# Power_5v_3v3.net
KiCad netlist of a schematic drawn in Altium Designer
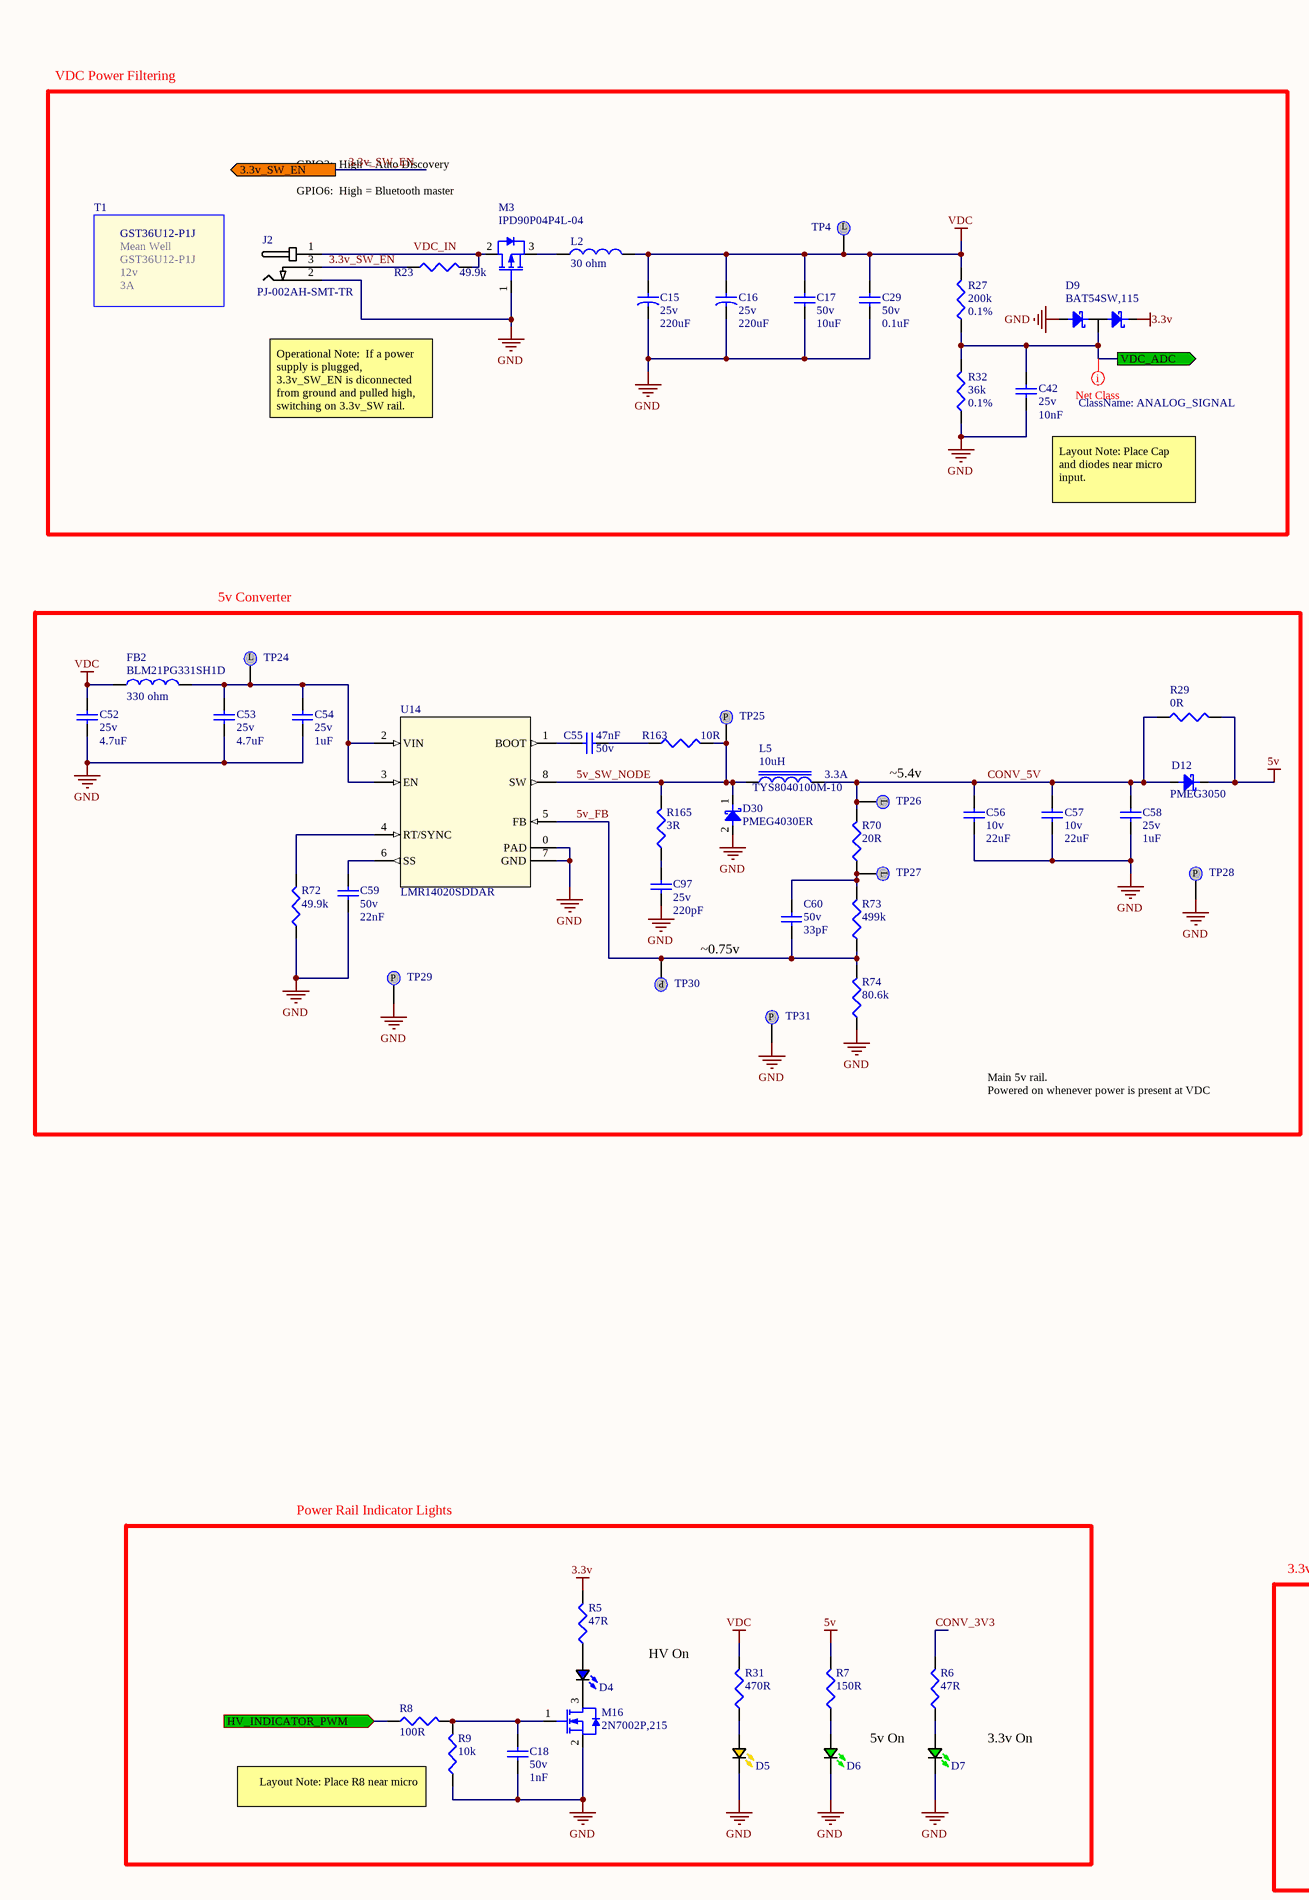
[diagram p0: Power_5v_3v3.SchDoc, left]
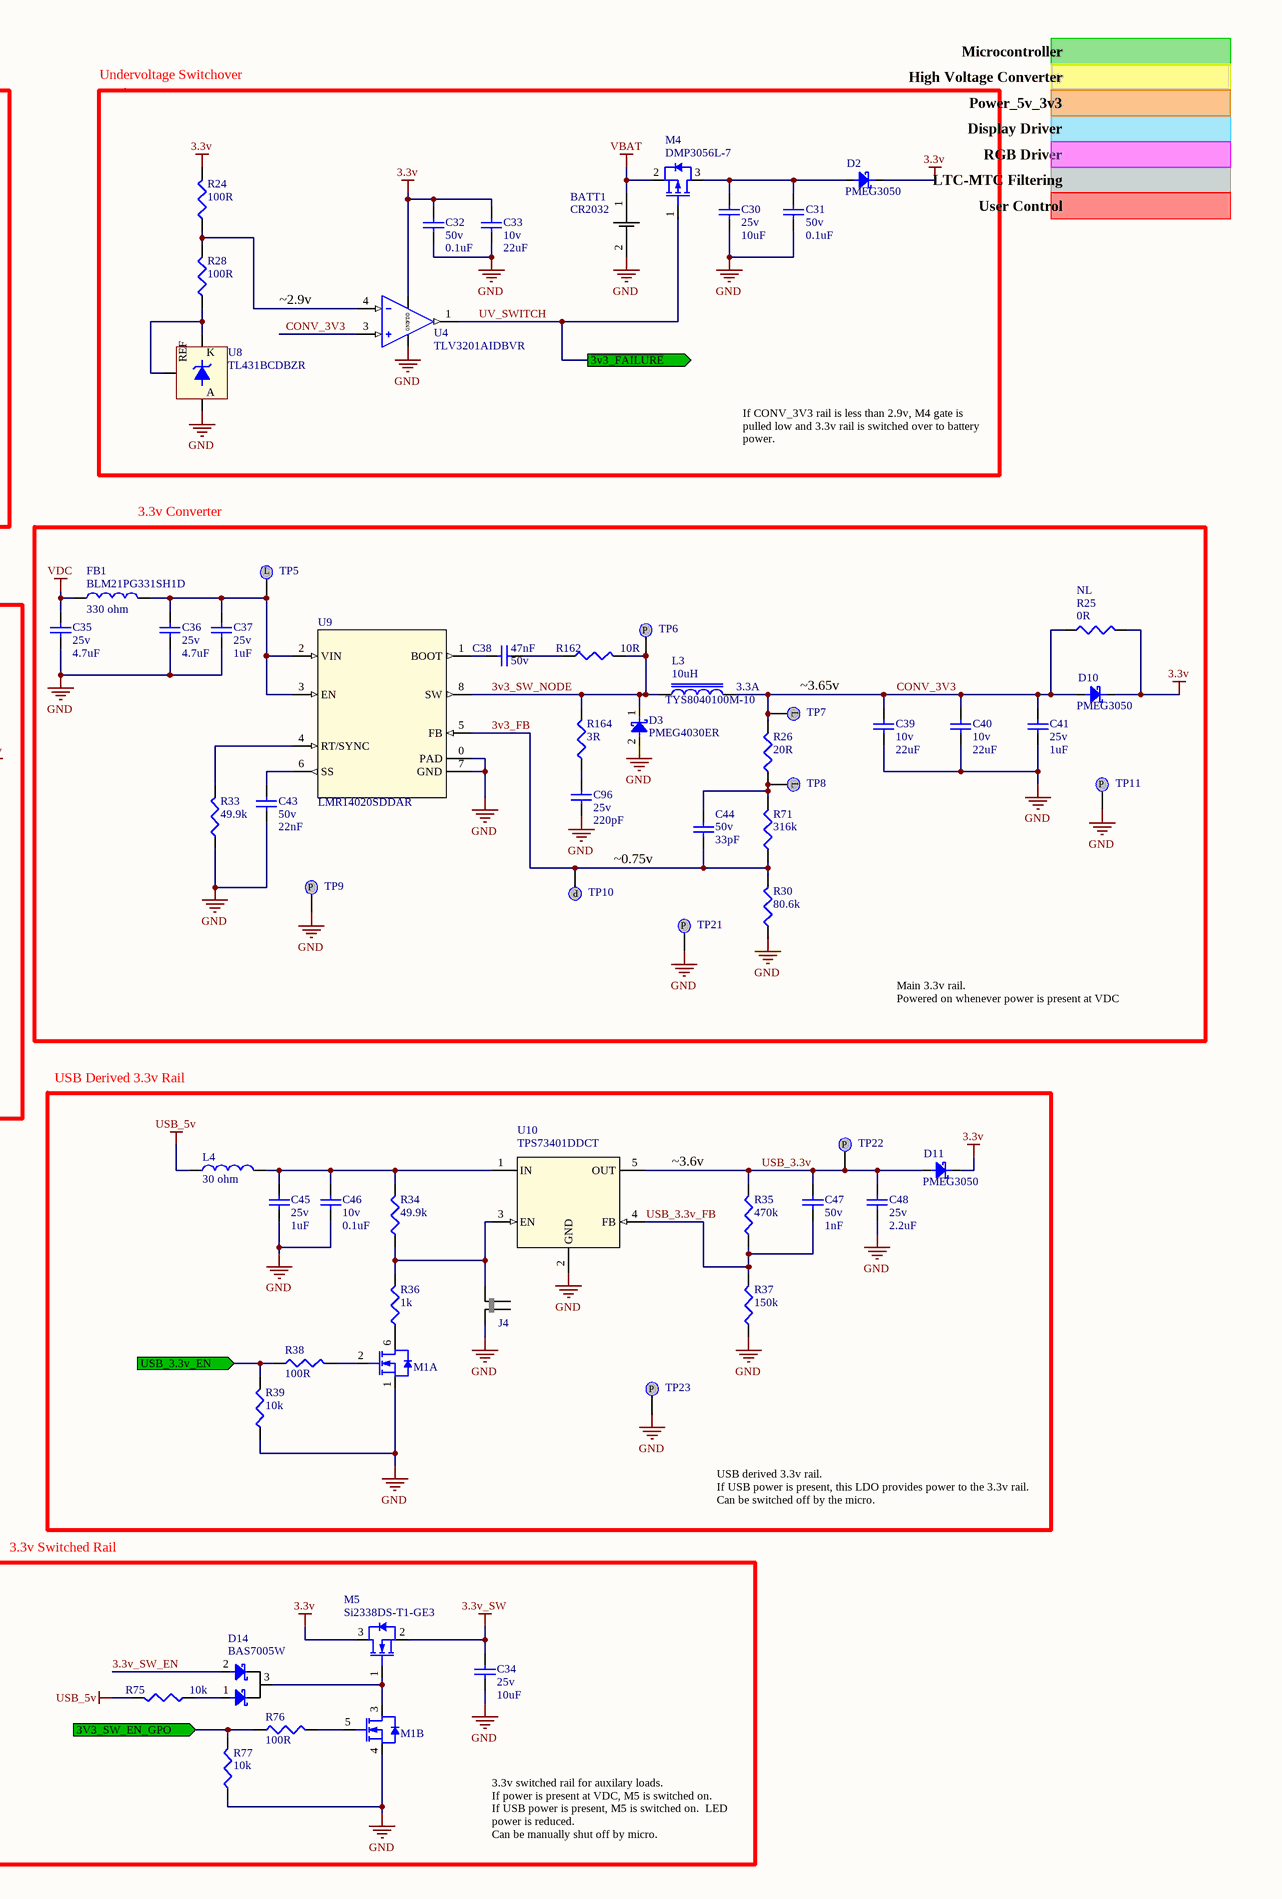
[diagram p1: Power_5v_3v3.SchDoc, right]

(export (version "E")
  (design (tool "Eeschema 10.0.6"))
  (components
    (comp (ref "BATT1")
      (value "CR2032")
      (footprint "2032 Holder")
      (description "SMD Coin Cell Holder for CR2032")
      (fields (field (name "MFG") "RENATA"))
      (libsource (lib "Altium Library") (part "2032 Coin Cell Holder"))
    )
    (comp (ref "C15")
      (value "220uF")
      (footprint "SMD ELEC CAP (D=6.3, L=7.7, H=8)")
      (fields
        (field (name "TOLERANCE") "20%")
        (field (name "MFG") "PANASONIC")
        (field (name "VOLTAGE") "25v")
      )
      (libsource (lib "Altium Library") (part "220uF / 25v"))
    )
    (comp (ref "C16")
      (value "220uF")
      (footprint "SMD ELEC CAP (D=6.3, L=7.7, H=8)")
      (fields
        (field (name "TOLERANCE") "20%")
        (field (name "MFG") "PANASONIC")
        (field (name "VOLTAGE") "25v")
      )
      (libsource (lib "Altium Library") (part "220uF / 25v"))
    )
    (comp (ref "C17")
      (value "10uF")
      (footprint "CAP1206R")
      (fields (field (name "TOLERANCE") "10%") (field (name "MFG") "TDK") (field (name "VOLTAGE") "50v"))
      (libsource (lib "Altium Library") (part "10uF 50v (1206)"))
    )
    (comp (ref "C18")
      (value "1nF")
      (footprint "CAP0402R")
      (fields (field (name "TOLERANCE") "10%") (field (name "MFG") "Vishay") (field (name "VOLTAGE") "50v"))
      (libsource (lib "Altium Library") (part "1nF 50v (0402)"))
    )
    (comp (ref "C29")
      (value "0.1uF")
      (footprint "CAP0603R")
      (fields (field (name "MFG") "Vishay") (field (name "VOLTAGE") "50v"))
      (libsource (lib "Altium Library") (part "0.1uF 50v (0603)"))
    )
    (comp (ref "C30")
      (value "10uF")
      (footprint "CAP1206R")
      (fields (field (name "TOLERANCE") "10%") (field (name "MFG") "MURATA") (field (name "VOLTAGE") "25v"))
      (libsource (lib "Altium Library") (part "10uF 25v (1206)"))
    )
    (comp (ref "C31")
      (value "0.1uF")
      (footprint "CAP0603R")
      (fields (field (name "MFG") "Vishay") (field (name "VOLTAGE") "50v"))
      (libsource (lib "Altium Library") (part "0.1uF 50v (0603)"))
    )
    (comp (ref "C32")
      (value "0.1uF")
      (footprint "CAP0603R")
      (fields (field (name "MFG") "Vishay") (field (name "VOLTAGE") "50v"))
      (libsource (lib "Altium Library") (part "0.1uF 50v (0603)"))
    )
    (comp (ref "C33")
      (value "22uF")
      (footprint "CAP1210R")
      (fields (field (name "TOLERANCE") "10%") (field (name "MFG") "MURATA") (field (name "VOLTAGE") "10v"))
      (libsource (lib "Altium Library") (part "22uF 10v (1210)"))
    )
    (comp (ref "C34")
      (value "10uF")
      (footprint "CAP1206R")
      (fields (field (name "TOLERANCE") "10%") (field (name "MFG") "MURATA") (field (name "VOLTAGE") "25v"))
      (libsource (lib "Altium Library") (part "10uF 25v (1206)"))
    )
    (comp (ref "C35")
      (value "4.7uF")
      (footprint "CAP1206R")
      (fields (field (name "TOLERANCE") "10%") (field (name "MFG") "Murata") (field (name "VOLTAGE") "25v"))
      (libsource (lib "Altium Library") (part "4.7uF 25v (1206)"))
    )
    (comp (ref "C36")
      (value "4.7uF")
      (footprint "CAP1206R")
      (fields (field (name "TOLERANCE") "10%") (field (name "MFG") "Murata") (field (name "VOLTAGE") "25v"))
      (libsource (lib "Altium Library") (part "4.7uF 25v (1206)"))
    )
    (comp (ref "C37")
      (value "1uF")
      (footprint "CAP0805R")
      (fields (field (name "MFG") "Vishay") (field (name "VOLTAGE") "25v"))
      (libsource (lib "Altium Library") (part "1uF 25v (0805)"))
    )
    (comp (ref "C38")
      (value "47nF")
      (footprint "CAP0603R")
      (fields (field (name "TOLERANCE") "10%") (field (name "MFG") "VISHAY") (field (name "VOLTAGE") "50v"))
      (libsource (lib "Altium Library") (part "47nF 50v (0603)"))
    )
    (comp (ref "C39")
      (value "22uF")
      (footprint "CAP1210R")
      (fields (field (name "TOLERANCE") "10%") (field (name "MFG") "MURATA") (field (name "VOLTAGE") "10v"))
      (libsource (lib "Altium Library") (part "22uF 10v (1210)"))
    )
    (comp (ref "C40")
      (value "22uF")
      (footprint "CAP1210R")
      (fields (field (name "TOLERANCE") "10%") (field (name "MFG") "MURATA") (field (name "VOLTAGE") "10v"))
      (libsource (lib "Altium Library") (part "22uF 10v (1210)"))
    )
    (comp (ref "C41")
      (value "1uF")
      (footprint "CAP0805R")
      (fields (field (name "MFG") "Vishay") (field (name "VOLTAGE") "25v"))
      (libsource (lib "Altium Library") (part "1uF 25v (0805)"))
    )
    (comp (ref "C42")
      (value "10nF")
      (footprint "CAP0402R")
      (fields (field (name "TOLERANCE") "5%") (field (name "MFG") "Vishay") (field (name "VOLTAGE") "25v"))
      (libsource (lib "Altium Library") (part "10nF 25v (0402)"))
    )
    (comp (ref "C43")
      (value "22nF")
      (footprint "CAP0603R")
      (fields (field (name "TOLERANCE") "5%") (field (name "VOLTAGE") "50v"))
      (libsource (lib "Altium Library") (part "22nF 50v (0603)"))
    )
    (comp (ref "C44")
      (value "33pF")
      (footprint "CAP0402R")
      (fields (field (name "TOLERANCE") "5%") (field (name "MFG") "Vishay") (field (name "VOLTAGE") "50v"))
      (libsource (lib "Altium Library") (part "33pF 50v (0402)"))
    )
    (comp (ref "C45")
      (value "1uF")
      (footprint "CAP0805R")
      (fields (field (name "MFG") "Vishay") (field (name "VOLTAGE") "25v"))
      (libsource (lib "Altium Library") (part "1uF 25v (0805)"))
    )
    (comp (ref "C46")
      (value "0.1uF")
      (footprint "CAP0402R")
      (fields (field (name "TOLERANCE") "20%") (field (name "MFG") "Vishay") (field (name "VOLTAGE") "10v"))
      (libsource (lib "Altium Library") (part "0.1uF 10v (0402)"))
    )
    (comp (ref "C47")
      (value "1nF")
      (footprint "CAP0402R")
      (fields (field (name "TOLERANCE") "10%") (field (name "MFG") "Vishay") (field (name "VOLTAGE") "50v"))
      (libsource (lib "Altium Library") (part "1nF 50v (0402)"))
    )
    (comp (ref "C48")
      (value "2.2uF")
      (footprint "CAP1206R")
      (fields (field (name "VOLTAGE") "25v"))
      (libsource (lib "Altium Library") (part "2.2uF 25v (1206)"))
    )
    (comp (ref "C52")
      (value "4.7uF")
      (footprint "CAP1206R")
      (fields (field (name "TOLERANCE") "10%") (field (name "MFG") "Murata") (field (name "VOLTAGE") "25v"))
      (libsource (lib "Altium Library") (part "4.7uF 25v (1206)"))
    )
    (comp (ref "C53")
      (value "4.7uF")
      (footprint "CAP1206R")
      (fields (field (name "TOLERANCE") "10%") (field (name "MFG") "Murata") (field (name "VOLTAGE") "25v"))
      (libsource (lib "Altium Library") (part "4.7uF 25v (1206)"))
    )
    (comp (ref "C54")
      (value "1uF")
      (footprint "CAP0805R")
      (fields (field (name "MFG") "Vishay") (field (name "VOLTAGE") "25v"))
      (libsource (lib "Altium Library") (part "1uF 25v (0805)"))
    )
    (comp (ref "C55")
      (value "47nF")
      (footprint "CAP0603R")
      (fields (field (name "TOLERANCE") "10%") (field (name "MFG") "VISHAY") (field (name "VOLTAGE") "50v"))
      (libsource (lib "Altium Library") (part "47nF 50v (0603)"))
    )
    (comp (ref "C56")
      (value "22uF")
      (footprint "CAP1210R")
      (fields (field (name "TOLERANCE") "10%") (field (name "MFG") "MURATA") (field (name "VOLTAGE") "10v"))
      (libsource (lib "Altium Library") (part "22uF 10v (1210)"))
    )
    (comp (ref "C57")
      (value "22uF")
      (footprint "CAP1210R")
      (fields (field (name "TOLERANCE") "10%") (field (name "MFG") "MURATA") (field (name "VOLTAGE") "10v"))
      (libsource (lib "Altium Library") (part "22uF 10v (1210)"))
    )
    (comp (ref "C58")
      (value "1uF")
      (footprint "CAP0805R")
      (fields (field (name "MFG") "Vishay") (field (name "VOLTAGE") "25v"))
      (libsource (lib "Altium Library") (part "1uF 25v (0805)"))
    )
    (comp (ref "C59")
      (value "22nF")
      (footprint "CAP0603R")
      (fields (field (name "TOLERANCE") "5%") (field (name "VOLTAGE") "50v"))
      (libsource (lib "Altium Library") (part "22nF 50v (0603)"))
    )
    (comp (ref "C60")
      (value "33pF")
      (footprint "CAP0402R")
      (fields (field (name "TOLERANCE") "5%") (field (name "MFG") "Vishay") (field (name "VOLTAGE") "50v"))
      (libsource (lib "Altium Library") (part "33pF 50v (0402)"))
    )
    (comp (ref "C96")
      (value "220pF")
      (footprint "CAP0402R")
      (fields (field (name "TOLERANCE") "5%") (field (name "MFG") "Murata") (field (name "VOLTAGE") "25v"))
      (libsource (lib "Altium Library") (part "220pF 25v (0402)"))
    )
    (comp (ref "C97")
      (value "220pF")
      (footprint "CAP0402R")
      (fields (field (name "TOLERANCE") "5%") (field (name "MFG") "Murata") (field (name "VOLTAGE") "25v"))
      (libsource (lib "Altium Library") (part "220pF 25v (0402)"))
    )
    (comp (ref "D2")
      (value "PMEG3050")
      (footprint "SOD128")
      (fields (field (name "MFG") "NXP"))
      (libsource (lib "Altium Library") (part "PMEG3050EP"))
    )
    (comp (ref "D3")
      (value "PMEG4030ER")
      (footprint "SOD-123")
      (fields (field (name "MFG") "NXP"))
      (libsource (lib "Altium Library") (part "PMEG4030ER"))
    )
    (comp (ref "D4")
      (value "LTST-C193TBKT-5A")
      (footprint "LED Blue 0603")
      (fields (field (name "MFG") "Lite On"))
      (libsource (lib "Altium Library") (part "LED Blue 0603"))
    )
    (comp (ref "D5")
      (value "LTST-C190AKT")
      (footprint "LED Amber 0603")
      (fields (field (name "MFG") "Lite On"))
      (libsource (lib "Altium Library") (part "LED Amber 0603"))
    )
    (comp (ref "D6")
      (value "LTST-S270KGKT")
      (footprint "LED Green 0603")
      (fields (field (name "MFG") "Lite On"))
      (libsource (lib "Altium Library") (part "LED Green 0603"))
    )
    (comp (ref "D7")
      (value "LTST-S270KGKT")
      (footprint "LED Green 0603")
      (fields (field (name "MFG") "Lite On"))
      (libsource (lib "Altium Library") (part "LED Green 0603"))
    )
    (comp (ref "D9")
      (value "BAT54SW,115")
      (footprint "SOT-323")
      (description "Series connected dual Schottky diode")
      (fields (field (name "MFG") "NXP"))
      (libsource (lib "Altium Library") (part "BAT54S"))
    )
    (comp (ref "D10")
      (value "PMEG3050")
      (footprint "SOD128")
      (fields (field (name "MFG") "NXP"))
      (libsource (lib "Altium Library") (part "PMEG3050EP"))
    )
    (comp (ref "D11")
      (value "PMEG3050")
      (footprint "SOD128")
      (fields (field (name "MFG") "NXP"))
      (libsource (lib "Altium Library") (part "PMEG3050EP"))
    )
    (comp (ref "D12")
      (value "PMEG3050")
      (footprint "SOD128")
      (fields (field (name "MFG") "NXP"))
      (libsource (lib "Altium Library") (part "PMEG3050EP"))
    )
    (comp (ref "D14")
      (value "BAS7005W")
      (footprint "SOT-323")
      (description "Schottky, Dual, Common Cathode")
      (fields (field (name "MFG") "Vishay"))
      (libsource (lib "Altium Library") (part "BAS7005WH6327XTSA1"))
    )
    (comp (ref "D30")
      (value "PMEG4030ER")
      (footprint "SOD-123")
      (fields (field (name "MFG") "NXP"))
      (libsource (lib "Altium Library") (part "PMEG4030ER"))
    )
    (comp (ref "FB1")
      (value "BLM21PG331SH1D")
      (footprint "RES0805R")
      (fields
        (field (name "MFG") "MURATA")
        (field (name "TOLERANCE") "20%")
        (field (name "IMPEDANCE") "330 ohm")
      )
      (libsource (lib "Altium Library") (part "BLM21PG331SH1D (0805)"))
    )
    (comp (ref "FB2")
      (value "BLM21PG331SH1D")
      (footprint "RES0805R")
      (fields
        (field (name "MFG") "MURATA")
        (field (name "TOLERANCE") "20%")
        (field (name "IMPEDANCE") "330 ohm")
      )
      (libsource (lib "Altium Library") (part "BLM21PG331SH1D (0805)"))
    )
    (comp (ref "J2")
      (value "PJ-002AH-SMT-TR")
      (footprint "PJ-002AH-SMT-TR")
      (description "2.0mm ID/6.5mm OD Barrel Plug")
      (fields (field (name "MFG") "CUI") (field (name "VOLTAGE") "16v"))
      (libsource (lib "Altium Library") (part "PJ-002AH-SMT-TR"))
    )
    (comp (ref "J4")
      (value "None")
      (footprint "Jumper_2.54mm_2x1")
      (description "Jumper_Single_2.54mm")
      (libsource (lib "Altium Library") (part "Jumper x1"))
    )
    (comp (ref "L2")
      (value "30 ohm")
      (footprint "RES0805R")
      (fields (field (name "MFG") "MURATA") (field (name "TOLERANCE") "20%"))
      (libsource (lib "Altium Library") (part "EMI Ferrite (0805)"))
    )
    (comp (ref "L3")
      (value "10uH")
      (footprint "TYS8040100M-10")
      (description "Inductor, 10uH, 3.3A")
      (fields
        (field (name "MFG") "LAIRD")
        (field (name "MFG_PN") "TYS8040100M-10")
        (field (name "CURRENT") "3.3A")
      )
      (libsource (lib "Altium Library") (part "10uH 3.3A"))
    )
    (comp (ref "L4")
      (value "30 ohm")
      (footprint "RES0805R")
      (fields (field (name "MFG") "MURATA") (field (name "TOLERANCE") "20%"))
      (libsource (lib "Altium Library") (part "EMI Ferrite (0805)"))
    )
    (comp (ref "L5")
      (value "10uH")
      (footprint "TYS8040100M-10")
      (description "Inductor, 10uH, 3.3A")
      (fields
        (field (name "MFG") "LAIRD")
        (field (name "MFG_PN") "TYS8040100M-10")
        (field (name "CURRENT") "3.3A")
      )
      (libsource (lib "Altium Library") (part "10uH 3.3A"))
    )
    (comp (ref "M1")
      (value "NX3020NAKV,115")
      (footprint "SOT666-6N")
      (description "NFET_DUAL_200mA_30v")
      (fields (field (name "MFG") "NXP"))
      (libsource (lib "Altium Library") (part "NX3020NAKV"))
    )
    (comp (ref "M3")
      (value "IPD90P04P4L-04")
      (footprint "DPAK2")
      (description "PFET_SINGLE_90A_40v")
      (fields (field (name "MFG") "INFINEON"))
      (libsource (lib "Altium Library") (part "IPD90P04P4L-04"))
    )
    (comp (ref "M4")
      (value "DMP3056L-7")
      (footprint "SOT23-3M")
      (description "PFET_SINGLE_4.3A_30v")
      (fields (field (name "MFG") "DIODES_INC"))
      (libsource (lib "Altium Library") (part "DMP3056L"))
    )
    (comp (ref "M5")
      (value "Si2338DS-T1-GE3")
      (footprint "SOT23-3M")
      (description "NFET_SINGLE_6A_30V")
      (fields (field (name "MFG") "VISHAY"))
      (libsource (lib "Altium Library") (part "Si2338DS"))
    )
    (comp (ref "M16")
      (value "2N7002P,215")
      (footprint "SOT23-3M")
      (description "NFET_SINGLE_360mA_60V")
      (fields (field (name "MFG") "NXP"))
      (libsource (lib "Altium Library") (part "2N7002"))
    )
    (comp (ref "R5")
      (value "47R")
      (footprint "RES0603R")
      (fields (field (name "TOLERANCE") "1%") (field (name "POWER") "0.1W") (field (name "MFG") "Vishay"))
      (libsource (lib "Altium Library") (part "47R (0603)"))
    )
    (comp (ref "R6")
      (value "47R")
      (footprint "RES0603R")
      (fields (field (name "TOLERANCE") "1%") (field (name "POWER") "0.1W") (field (name "MFG") "Vishay"))
      (libsource (lib "Altium Library") (part "47R (0603)"))
    )
    (comp (ref "R7")
      (value "150R")
      (footprint "RES0603R")
      (fields (field (name "TOLERANCE") "1%") (field (name "POWER") "0.1W") (field (name "MFG") "Vishay"))
      (libsource (lib "Altium Library") (part "150R (0603)"))
    )
    (comp (ref "R8")
      (value "100R")
      (footprint "RES0402R")
      (fields (field (name "TOLERANCE") "1%") (field (name "POWER") "63mW") (field (name "MFG") "Vishay"))
      (libsource (lib "Altium Library") (part "100R (0402)"))
    )
    (comp (ref "R9")
      (value "10k")
      (footprint "RES0402R")
      (fields (field (name "TOLERANCE") "1%") (field (name "POWER") "63mW") (field (name "MFG") "Vishay"))
      (libsource (lib "Altium Library") (part "10k (0402)"))
    )
    (comp (ref "R23")
      (value "49.9k")
      (footprint "RES0402R")
      (fields (field (name "TOLERANCE") "1%") (field (name "POWER") "63mW") (field (name "MFG") "Vishay"))
      (libsource (lib "Altium Library") (part "49.9k (0402)"))
    )
    (comp (ref "R24")
      (value "100R")
      (footprint "RES0402R")
      (fields (field (name "TOLERANCE") "1%") (field (name "POWER") "63mW") (field (name "MFG") "Vishay"))
      (libsource (lib "Altium Library") (part "100R (0402)"))
    )
    (comp (ref "R25")
      (value "0R")
      (footprint "RES1206R")
      (description "0R, 1206")
      (fields (field (name "MFG") "Vishay") (field (name "LOAD") "NL"))
      (libsource (lib "Altium Library") (part "0R (1206)"))
    )
    (comp (ref "R26")
      (value "20R")
      (footprint "RES0402R")
      (fields (field (name "TOLERANCE") "1%") (field (name "POWER") "63mW") (field (name "MFG") "Vishay"))
      (libsource (lib "Altium Library") (part "20R (0402)"))
    )
    (comp (ref "R27")
      (value "200k")
      (footprint "RES0402R")
      (fields (field (name "POWER") "63mW") (field (name "MFG") "Vishay") (field (name "TOLERANCE") "0.1%"))
      (libsource (lib "Altium Library") (part "200k   0.1% (0402)"))
    )
    (comp (ref "R28")
      (value "100R")
      (footprint "RES0402R")
      (fields (field (name "TOLERANCE") "1%") (field (name "POWER") "63mW") (field (name "MFG") "Vishay"))
      (libsource (lib "Altium Library") (part "100R (0402)"))
    )
    (comp (ref "R29")
      (value "0R")
      (footprint "RES1206R")
      (description "0R, 1206")
      (fields (field (name "MFG") "Vishay"))
      (libsource (lib "Altium Library") (part "0R (1206)"))
    )
    (comp (ref "R30")
      (value "80.6k")
      (footprint "RES0402R")
      (fields (field (name "TOLERANCE") "1%") (field (name "POWER") "63mW") (field (name "MFG") "Vishay"))
      (libsource (lib "Altium Library") (part "80.6k (0402)"))
    )
    (comp (ref "R31")
      (value "470R")
      (footprint "RES0603R")
      (fields (field (name "TOLERANCE") "1%") (field (name "POWER") "0.1W") (field (name "MFG") "Vishay"))
      (libsource (lib "Altium Library") (part "470R (0603)"))
    )
    (comp (ref "R32")
      (value "36k")
      (footprint "RES0402R")
      (fields (field (name "POWER") "63mW") (field (name "MFG") "Vishay") (field (name "TOLERANCE") "0.1%"))
      (libsource (lib "Altium Library") (part "36k   0.1% (0402)"))
    )
    (comp (ref "R33")
      (value "49.9k")
      (footprint "RES0402R")
      (fields (field (name "TOLERANCE") "1%") (field (name "POWER") "63mW") (field (name "MFG") "Vishay"))
      (libsource (lib "Altium Library") (part "49.9k (0402)"))
    )
    (comp (ref "R34")
      (value "49.9k")
      (footprint "RES0402R")
      (fields (field (name "TOLERANCE") "1%") (field (name "POWER") "63mW") (field (name "MFG") "Vishay"))
      (libsource (lib "Altium Library") (part "49.9k (0402)"))
    )
    (comp (ref "R35")
      (value "470k")
      (footprint "RES0402R")
      (fields (field (name "TOLERANCE") "1%") (field (name "POWER") "63mW") (field (name "MFG") "Vishay"))
      (libsource (lib "Altium Library") (part "470k (0402)"))
    )
    (comp (ref "R36")
      (value "1k")
      (footprint "RES0402R")
      (fields (field (name "TOLERANCE") "1%") (field (name "POWER") "63mW") (field (name "MFG") "Vishay"))
      (libsource (lib "Altium Library") (part "1k (0402)"))
    )
    (comp (ref "R37")
      (value "150k")
      (footprint "RES0402R")
      (fields (field (name "TOLERANCE") "1%") (field (name "POWER") "63mW") (field (name "MFG") "Vishay"))
      (libsource (lib "Altium Library") (part "150k (0402)"))
    )
    (comp (ref "R38")
      (value "100R")
      (footprint "RES0402R")
      (fields (field (name "TOLERANCE") "1%") (field (name "POWER") "63mW") (field (name "MFG") "Vishay"))
      (libsource (lib "Altium Library") (part "100R (0402)"))
    )
    (comp (ref "R39")
      (value "10k")
      (footprint "RES0402R")
      (fields (field (name "TOLERANCE") "1%") (field (name "POWER") "63mW") (field (name "MFG") "Vishay"))
      (libsource (lib "Altium Library") (part "10k (0402)"))
    )
    (comp (ref "R70")
      (value "20R")
      (footprint "RES0402R")
      (fields (field (name "TOLERANCE") "1%") (field (name "POWER") "63mW") (field (name "MFG") "Vishay"))
      (libsource (lib "Altium Library") (part "20R (0402)"))
    )
    (comp (ref "R71")
      (value "316k")
      (footprint "RES0402R")
      (fields (field (name "TOLERANCE") "1%") (field (name "POWER") "63mW") (field (name "MFG") "Vishay"))
      (libsource (lib "Altium Library") (part "316k (0402)"))
    )
    (comp (ref "R72")
      (value "49.9k")
      (footprint "RES0402R")
      (fields (field (name "TOLERANCE") "1%") (field (name "POWER") "63mW") (field (name "MFG") "Vishay"))
      (libsource (lib "Altium Library") (part "49.9k (0402)"))
    )
    (comp (ref "R73")
      (value "499k")
      (footprint "RES0402R")
      (fields (field (name "TOLERANCE") "1%") (field (name "POWER") "63mW") (field (name "MFG") "Vishay"))
      (libsource (lib "Altium Library") (part "499k (0402)"))
    )
    (comp (ref "R74")
      (value "80.6k")
      (footprint "RES0402R")
      (fields (field (name "TOLERANCE") "1%") (field (name "POWER") "63mW") (field (name "MFG") "Vishay"))
      (libsource (lib "Altium Library") (part "80.6k (0402)"))
    )
    (comp (ref "R75")
      (value "10k")
      (footprint "RES0402R")
      (fields (field (name "TOLERANCE") "1%") (field (name "POWER") "63mW") (field (name "MFG") "Vishay"))
      (libsource (lib "Altium Library") (part "10k (0402)"))
    )
    (comp (ref "R76")
      (value "100R")
      (footprint "RES0402R")
      (fields (field (name "TOLERANCE") "1%") (field (name "POWER") "63mW") (field (name "MFG") "Vishay"))
      (libsource (lib "Altium Library") (part "100R (0402)"))
    )
    (comp (ref "R77")
      (value "10k")
      (footprint "RES0402R")
      (fields (field (name "TOLERANCE") "1%") (field (name "POWER") "63mW") (field (name "MFG") "Vishay"))
      (libsource (lib "Altium Library") (part "10k (0402)"))
    )
    (comp (ref "R162")
      (value "10R")
      (footprint "RES0402R")
      (fields (field (name "TOLERANCE") "1%") (field (name "POWER") "63mW") (field (name "MFG") "Vishay"))
      (libsource (lib "Altium Library") (part "10R (0402)"))
    )
    (comp (ref "R163")
      (value "10R")
      (footprint "RES0402R")
      (fields (field (name "TOLERANCE") "1%") (field (name "POWER") "63mW") (field (name "MFG") "Vishay"))
      (libsource (lib "Altium Library") (part "10R (0402)"))
    )
    (comp (ref "R164")
      (value "3R")
      (footprint "RES0603R")
      (fields (field (name "TOLERANCE") "1%") (field (name "POWER") "0.1W") (field (name "MFG") "Vishay"))
      (libsource (lib "Altium Library") (part "3R (0603)"))
    )
    (comp (ref "R165")
      (value "3R")
      (footprint "RES0603R")
      (fields (field (name "TOLERANCE") "1%") (field (name "POWER") "0.1W") (field (name "MFG") "Vishay"))
      (libsource (lib "Altium Library") (part "3R (0603)"))
    )
    (comp (ref "T1")
      (value "GST36U12-P1J")
      (description "12v/3A Wall Mount AC Adapter")
      (fields
        (field (name "MFG") "Mean Well")
        (field (name "MFG_PN") "GST36U12-P1J")
        (field (name "VOUT") "12v")
        (field (name "CURRENT") "3A")
      )
      (libsource (lib "Altium Library") (part "GST36U12-P1J"))
    )
    (comp (ref "TP4")
      (value "5001")
      (footprint "5001 Testpoint")
      (fields (field (name "MFG") "KEYSTONE"))
      (libsource (lib "Altium Library") (part "Testpoint Loop"))
    )
    (comp (ref "TP5")
      (value "5001")
      (footprint "5001 Testpoint")
      (fields (field (name "MFG") "KEYSTONE"))
      (libsource (lib "Altium Library") (part "Testpoint Loop"))
    )
    (comp (ref "TP6")
      (value "NONE")
      (footprint "TESTPOINT - 1.5mm Round Pad")
      (description "1.5mm Testpoint")
      (libsource (lib "Altium Library") (part "Testpoint 1.5mm Pad"))
    )
    (comp (ref "TP7")
      (value "5001")
      (footprint "5001 Testpoint")
      (fields (field (name "MFG") "KEYSTONE"))
      (libsource (lib "Altium Library") (part "Testpoint Loop"))
    )
    (comp (ref "TP8")
      (value "5001")
      (footprint "5001 Testpoint")
      (fields (field (name "MFG") "KEYSTONE"))
      (libsource (lib "Altium Library") (part "Testpoint Loop"))
    )
    (comp (ref "TP9")
      (value "NONE")
      (footprint "TESTPOINT - 1.5mm Round Pad")
      (description "1.5mm Testpoint")
      (libsource (lib "Altium Library") (part "Testpoint 1.5mm Pad"))
    )
    (comp (ref "TP10")
      (value "NONE")
      (footprint "TESTPOINT - 1.5mm Round Pad")
      (description "1.5mm Testpoint")
      (libsource (lib "Altium Library") (part "Testpoint 1.5mm Pad"))
    )
    (comp (ref "TP11")
      (value "NONE")
      (footprint "TESTPOINT - 1.5mm Round Pad")
      (description "1.5mm Testpoint")
      (libsource (lib "Altium Library") (part "Testpoint 1.5mm Pad"))
    )
    (comp (ref "TP21")
      (value "NONE")
      (footprint "TESTPOINT - 1.5mm Round Pad")
      (description "1.5mm Testpoint")
      (libsource (lib "Altium Library") (part "Testpoint 1.5mm Pad"))
    )
    (comp (ref "TP22")
      (value "NONE")
      (footprint "TESTPOINT - 1.5mm Round Pad")
      (description "1.5mm Testpoint")
      (libsource (lib "Altium Library") (part "Testpoint 1.5mm Pad"))
    )
    (comp (ref "TP23")
      (value "NONE")
      (footprint "TESTPOINT - 1.5mm Round Pad")
      (description "1.5mm Testpoint")
      (libsource (lib "Altium Library") (part "Testpoint 1.5mm Pad"))
    )
    (comp (ref "TP24")
      (value "5001")
      (footprint "5001 Testpoint")
      (fields (field (name "MFG") "KEYSTONE"))
      (libsource (lib "Altium Library") (part "Testpoint Loop"))
    )
    (comp (ref "TP25")
      (value "NONE")
      (footprint "TESTPOINT - 1.5mm Round Pad")
      (description "1.5mm Testpoint")
      (libsource (lib "Altium Library") (part "Testpoint 1.5mm Pad"))
    )
    (comp (ref "TP26")
      (value "5001")
      (footprint "5001 Testpoint")
      (fields (field (name "MFG") "KEYSTONE"))
      (libsource (lib "Altium Library") (part "Testpoint Loop"))
    )
    (comp (ref "TP27")
      (value "5001")
      (footprint "5001 Testpoint")
      (fields (field (name "MFG") "KEYSTONE"))
      (libsource (lib "Altium Library") (part "Testpoint Loop"))
    )
    (comp (ref "TP28")
      (value "NONE")
      (footprint "TESTPOINT - 1.5mm Round Pad")
      (description "1.5mm Testpoint")
      (libsource (lib "Altium Library") (part "Testpoint 1.5mm Pad"))
    )
    (comp (ref "TP29")
      (value "NONE")
      (footprint "TESTPOINT - 1.5mm Round Pad")
      (description "1.5mm Testpoint")
      (libsource (lib "Altium Library") (part "Testpoint 1.5mm Pad"))
    )
    (comp (ref "TP30")
      (value "NONE")
      (footprint "TESTPOINT - 1.5mm Round Pad")
      (description "1.5mm Testpoint")
      (libsource (lib "Altium Library") (part "Testpoint 1.5mm Pad"))
    )
    (comp (ref "TP31")
      (value "NONE")
      (footprint "TESTPOINT - 1.5mm Round Pad")
      (description "1.5mm Testpoint")
      (libsource (lib "Altium Library") (part "Testpoint 1.5mm Pad"))
    )
    (comp (ref "U4")
      (value "TLV3201AIDBVR")
      (footprint "SOT23-5")
      (description "High Speed Analog Comparator")
      (fields (field (name "MFG") "TI"))
      (libsource (lib "Altium Library") (part "TLV3201AIDBVR"))
    )
    (comp (ref "U8")
      (value "TL431BCDBZR")
      (footprint "SOT23-3M")
      (description "Voltage Reference")
      (fields (field (name "MFG") "TI"))
      (libsource (lib "Altium Library") (part "TL431"))
    )
    (comp (ref "U9")
      (value "LMR14020SDDAR")
      (footprint "HSOIC-8")
      (description "Buck Regulator, Adjustable, 2A")
      (fields (field (name "MFG") "TI"))
      (libsource (lib "Altium Library") (part "LMR14020SDDAR"))
    )
    (comp (ref "U10")
      (value "TPS73401DDCT")
      (footprint "SOT23-5")
      (description "TPS73401DDCT, LDO, 250mA, Adj")
      (fields (field (name "MFG") "TI"))
      (libsource (lib "Altium Library") (part "TPS73401DDCT"))
    )
    (comp (ref "U14")
      (value "LMR14020SDDAR")
      (footprint "HSOIC-8")
      (description "Buck Regulator, Adjustable, 2A")
      (fields (field (name "MFG") "TI"))
      (libsource (lib "Altium Library") (part "LMR14020SDDAR"))
    )
  )
  (nets
    (net (code "1") (name "/3.3v_SW_EN") (class "Default")
      (node (ref "D14") (pin "2") (pinfunction "A2_2") (pintype "passive"))
      (node (ref "J2") (pin "3") (pinfunction "SWITCH_3") (pintype "passive"))
      (node (ref "R23") (pin "1") (pinfunction "1_1") (pintype "passive"))
    )
    (net (code "2") (name "/3V3_SW_EN_GPO") (class "Default")
      (node (ref "R76") (pin "1") (pinfunction "1_1") (pintype "passive"))
      (node (ref "R77") (pin "2") (pinfunction "2_2") (pintype "passive"))
    )
    (net (code "3") (name "/3v3_FB") (class "Default")
      (node (ref "C44") (pin "2") (pinfunction "2_2") (pintype "passive"))
      (node (ref "R30") (pin "2") (pinfunction "2_2") (pintype "passive"))
      (node (ref "R71") (pin "1") (pinfunction "1_1") (pintype "passive"))
      (node (ref "TP10") (pin "1") (pinfunction "1_1") (pintype "passive"))
      (node (ref "U9") (pin "5") (pinfunction "FB_5") (pintype "input"))
    )
    (net (code "4") (name "/3v3_SW_NODE") (class "Default")
      (node (ref "D3") (pin "1") (pinfunction "K_1") (pintype "passive"))
      (node (ref "L3") (pin "1") (pinfunction "1_1") (pintype "passive"))
      (node (ref "R162") (pin "2") (pinfunction "2_2") (pintype "passive"))
      (node (ref "R164") (pin "2") (pinfunction "2_2") (pintype "passive"))
      (node (ref "TP6") (pin "1") (pinfunction "1_1") (pintype "passive"))
      (node (ref "U9") (pin "8") (pinfunction "SW_8") (pintype "output"))
    )
    (net (code "5") (name "/5v_FB") (class "Default")
      (node (ref "C60") (pin "2") (pinfunction "2_2") (pintype "passive"))
      (node (ref "R73") (pin "1") (pinfunction "1_1") (pintype "passive"))
      (node (ref "R74") (pin "2") (pinfunction "2_2") (pintype "passive"))
      (node (ref "TP30") (pin "1") (pinfunction "1_1") (pintype "passive"))
      (node (ref "U14") (pin "5") (pinfunction "FB_5") (pintype "input"))
    )
    (net (code "6") (name "/5v_SW_NODE") (class "Default")
      (node (ref "D30") (pin "1") (pinfunction "K_1") (pintype "passive"))
      (node (ref "L5") (pin "1") (pinfunction "1_1") (pintype "passive"))
      (node (ref "R163") (pin "2") (pinfunction "2_2") (pintype "passive"))
      (node (ref "R165") (pin "2") (pinfunction "2_2") (pintype "passive"))
      (node (ref "TP25") (pin "1") (pinfunction "1_1") (pintype "passive"))
      (node (ref "U14") (pin "8") (pinfunction "SW_8") (pintype "output"))
    )
    (net (code "7") (name "/CONV_3V3") (class "Default")
      (node (ref "C39") (pin "1") (pinfunction "1_1") (pintype "passive"))
      (node (ref "C40") (pin "1") (pinfunction "1_1") (pintype "passive"))
      (node (ref "C41") (pin "1") (pinfunction "1_1") (pintype "passive"))
      (node (ref "D10") (pin "2") (pinfunction "A_2") (pintype "passive"))
      (node (ref "L3") (pin "2") (pinfunction "2_2") (pintype "passive"))
      (node (ref "R25") (pin "1") (pinfunction "1_1") (pintype "passive"))
      (node (ref "R26") (pin "2") (pinfunction "2_2") (pintype "passive"))
      (node (ref "R6") (pin "2") (pinfunction "2_2") (pintype "passive"))
      (node (ref "TP7") (pin "1") (pinfunction "1_1") (pintype "passive"))
      (node (ref "U4") (pin "3") (pinfunction "+_3") (pintype "input"))
    )
    (net (code "8") (name "/CONV_5V") (class "Default")
      (node (ref "C56") (pin "1") (pinfunction "1_1") (pintype "passive"))
      (node (ref "C57") (pin "1") (pinfunction "1_1") (pintype "passive"))
      (node (ref "C58") (pin "1") (pinfunction "1_1") (pintype "passive"))
      (node (ref "D12") (pin "2") (pinfunction "A_2") (pintype "passive"))
      (node (ref "L5") (pin "2") (pinfunction "2_2") (pintype "passive"))
      (node (ref "R29") (pin "1") (pinfunction "1_1") (pintype "passive"))
      (node (ref "R70") (pin "2") (pinfunction "2_2") (pintype "passive"))
      (node (ref "TP26") (pin "1") (pinfunction "1_1") (pintype "passive"))
    )
    (net (code "9") (name "/HV_INDICATOR_PWM") (class "Default")
      (node (ref "R8") (pin "1") (pinfunction "1_1") (pintype "passive"))
    )
    (net (code "10") (name "/USB_3.3v") (class "Default")
      (node (ref "C47") (pin "1") (pinfunction "1_1") (pintype "passive"))
      (node (ref "C48") (pin "1") (pinfunction "1_1") (pintype "passive"))
      (node (ref "D11") (pin "2") (pinfunction "A_2") (pintype "passive"))
      (node (ref "R35") (pin "2") (pinfunction "2_2") (pintype "passive"))
      (node (ref "TP22") (pin "1") (pinfunction "1_1") (pintype "passive"))
      (node (ref "U10") (pin "5") (pinfunction "OUT_5") (pintype "power_in"))
    )
    (net (code "11") (name "/USB_3.3v_EN") (class "Default")
      (node (ref "R38") (pin "1") (pinfunction "1_1") (pintype "passive"))
      (node (ref "R39") (pin "2") (pinfunction "2_2") (pintype "passive"))
    )
    (net (code "12") (name "/USB_3.3v_FB") (class "Default")
      (node (ref "C47") (pin "2") (pinfunction "2_2") (pintype "passive"))
      (node (ref "R35") (pin "1") (pinfunction "1_1") (pintype "passive"))
      (node (ref "R37") (pin "2") (pinfunction "2_2") (pintype "passive"))
      (node (ref "U10") (pin "4") (pinfunction "FB_4") (pintype "input"))
    )
    (net (code "13") (name "/UV_SWITCH") (class "Default")
      (node (ref "M4") (pin "1") (pinfunction "GATE_1") (pintype "passive"))
      (node (ref "U4") (pin "1") (pinfunction "OUT_1") (pintype "output"))
    )
    (net (code "14") (name "/VDC_ADC") (class "Default")
      (node (ref "C42") (pin "1") (pinfunction "1_1") (pintype "passive"))
      (node (ref "D9") (pin "3") (pinfunction "AK_3") (pintype "passive"))
      (node (ref "R27") (pin "1") (pinfunction "1_1") (pintype "passive"))
      (node (ref "R32") (pin "2") (pinfunction "2_2") (pintype "passive"))
    )
    (net (code "15") (name "/VDC_IN") (class "Default")
      (node (ref "J2") (pin "1") (pinfunction "PIN_1") (pintype "passive"))
      (node (ref "M3") (pin "2") (pinfunction "DRAIN_2") (pintype "passive"))
      (node (ref "R23") (pin "2") (pinfunction "2_2") (pintype "passive"))
    )
    (net (code "16") (name "3.3v") (class "Default")
      (node (ref "C32") (pin "1") (pinfunction "1_1") (pintype "passive"))
      (node (ref "C33") (pin "1") (pinfunction "1_1") (pintype "passive"))
      (node (ref "D10") (pin "1") (pinfunction "K_1") (pintype "passive"))
      (node (ref "D11") (pin "1") (pinfunction "K_1") (pintype "passive"))
      (node (ref "D2") (pin "1") (pinfunction "K_1") (pintype "passive"))
      (node (ref "D9") (pin "2") (pinfunction "A_2") (pintype "passive"))
      (node (ref "M5") (pin "3") (pinfunction "DRAIN_3") (pintype "passive"))
      (node (ref "R24") (pin "2") (pinfunction "2_2") (pintype "passive"))
      (node (ref "R25") (pin "2") (pinfunction "2_2") (pintype "passive"))
      (node (ref "R5") (pin "2") (pinfunction "2_2") (pintype "passive"))
      (node (ref "U4") (pin "5") (pinfunction "VDD_5") (pintype "passive"))
    )
    (net (code "17") (name "3.3v_SW") (class "Default")
      (node (ref "C34") (pin "1") (pinfunction "1_1") (pintype "passive"))
      (node (ref "M5") (pin "2") (pinfunction "SOURCE_2") (pintype "passive"))
    )
    (net (code "18") (name "5v") (class "Default")
      (node (ref "D12") (pin "1") (pinfunction "K_1") (pintype "passive"))
      (node (ref "R29") (pin "2") (pinfunction "2_2") (pintype "passive"))
      (node (ref "R7") (pin "2") (pinfunction "2_2") (pintype "passive"))
    )
    (net (code "19") (name "GND") (class "Default")
      (node (ref "BATT1") (pin "2") (pinfunction "2_2") (pintype "passive"))
      (node (ref "C15") (pin "1") (pinfunction "1_1") (pintype "passive"))
      (node (ref "C16") (pin "1") (pinfunction "1_1") (pintype "passive"))
      (node (ref "C17") (pin "2") (pinfunction "2_2") (pintype "passive"))
      (node (ref "C18") (pin "2") (pinfunction "2_2") (pintype "passive"))
      (node (ref "C29") (pin "2") (pinfunction "2_2") (pintype "passive"))
      (node (ref "C30") (pin "2") (pinfunction "2_2") (pintype "passive"))
      (node (ref "C31") (pin "2") (pinfunction "2_2") (pintype "passive"))
      (node (ref "C32") (pin "2") (pinfunction "2_2") (pintype "passive"))
      (node (ref "C33") (pin "2") (pinfunction "2_2") (pintype "passive"))
      (node (ref "C34") (pin "2") (pinfunction "2_2") (pintype "passive"))
      (node (ref "C35") (pin "2") (pinfunction "2_2") (pintype "passive"))
      (node (ref "C36") (pin "2") (pinfunction "2_2") (pintype "passive"))
      (node (ref "C37") (pin "2") (pinfunction "2_2") (pintype "passive"))
      (node (ref "C39") (pin "2") (pinfunction "2_2") (pintype "passive"))
      (node (ref "C40") (pin "2") (pinfunction "2_2") (pintype "passive"))
      (node (ref "C41") (pin "2") (pinfunction "2_2") (pintype "passive"))
      (node (ref "C42") (pin "2") (pinfunction "2_2") (pintype "passive"))
      (node (ref "C43") (pin "2") (pinfunction "2_2") (pintype "passive"))
      (node (ref "C45") (pin "2") (pinfunction "2_2") (pintype "passive"))
      (node (ref "C46") (pin "2") (pinfunction "2_2") (pintype "passive"))
      (node (ref "C48") (pin "2") (pinfunction "2_2") (pintype "passive"))
      (node (ref "C52") (pin "2") (pinfunction "2_2") (pintype "passive"))
      (node (ref "C53") (pin "2") (pinfunction "2_2") (pintype "passive"))
      (node (ref "C54") (pin "2") (pinfunction "2_2") (pintype "passive"))
      (node (ref "C56") (pin "2") (pinfunction "2_2") (pintype "passive"))
      (node (ref "C57") (pin "2") (pinfunction "2_2") (pintype "passive"))
      (node (ref "C58") (pin "2") (pinfunction "2_2") (pintype "passive"))
      (node (ref "C59") (pin "2") (pinfunction "2_2") (pintype "passive"))
      (node (ref "C96") (pin "2") (pinfunction "2_2") (pintype "passive"))
      (node (ref "C97") (pin "2") (pinfunction "2_2") (pintype "passive"))
      (node (ref "D3") (pin "2") (pinfunction "A_2") (pintype "passive"))
      (node (ref "D30") (pin "2") (pinfunction "A_2") (pintype "passive"))
      (node (ref "D5") (pin "1") (pinfunction "K_1") (pintype "passive"))
      (node (ref "D6") (pin "1") (pinfunction "K_1") (pintype "passive"))
      (node (ref "D7") (pin "1") (pinfunction "K_1") (pintype "passive"))
      (node (ref "D9") (pin "1") (pinfunction "A_1") (pintype "passive"))
      (node (ref "J2") (pin "2") (pinfunction "RING_2") (pintype "passive"))
      (node (ref "J4") (pin "1") (pinfunction "1_1") (pintype "passive"))
      (node (ref "M1") (pin "1") (pinfunction "S1_1") (pintype "passive"))
      (node (ref "M1") (pin "4") (pinfunction "S2_4") (pintype "passive"))
      (node (ref "M16") (pin "2") (pinfunction "SOURCE_2") (pintype "passive"))
      (node (ref "M3") (pin "1") (pinfunction "GATE_1") (pintype "passive"))
      (node (ref "R30") (pin "1") (pinfunction "1_1") (pintype "passive"))
      (node (ref "R32") (pin "1") (pinfunction "1_1") (pintype "passive"))
      (node (ref "R33") (pin "1") (pinfunction "1_1") (pintype "passive"))
      (node (ref "R37") (pin "1") (pinfunction "1_1") (pintype "passive"))
      (node (ref "R39") (pin "1") (pinfunction "1_1") (pintype "passive"))
      (node (ref "R72") (pin "1") (pinfunction "1_1") (pintype "passive"))
      (node (ref "R74") (pin "1") (pinfunction "1_1") (pintype "passive"))
      (node (ref "R77") (pin "1") (pinfunction "1_1") (pintype "passive"))
      (node (ref "R9") (pin "1") (pinfunction "1_1") (pintype "passive"))
      (node (ref "TP11") (pin "1") (pinfunction "1_1") (pintype "passive"))
      (node (ref "TP21") (pin "1") (pinfunction "1_1") (pintype "passive"))
      (node (ref "TP23") (pin "1") (pinfunction "1_1") (pintype "passive"))
      (node (ref "TP28") (pin "1") (pinfunction "1_1") (pintype "passive"))
      (node (ref "TP29") (pin "1") (pinfunction "1_1") (pintype "passive"))
      (node (ref "TP31") (pin "1") (pinfunction "1_1") (pintype "passive"))
      (node (ref "TP9") (pin "1") (pinfunction "1_1") (pintype "passive"))
      (node (ref "U10") (pin "2") (pinfunction "GND_2") (pintype "power_in"))
      (node (ref "U14") (pin "0") (pinfunction "PAD_0") (pintype "power_in"))
      (node (ref "U14") (pin "7") (pinfunction "GND_7") (pintype "power_in"))
      (node (ref "U4") (pin "2") (pinfunction "GND_2") (pintype "passive"))
      (node (ref "U8") (pin "3") (pinfunction "A_3") (pintype "power_in"))
      (node (ref "U9") (pin "0") (pinfunction "PAD_0") (pintype "power_in"))
      (node (ref "U9") (pin "7") (pinfunction "GND_7") (pintype "power_in"))
    )
    (net (code "20") (name "Net-(C38-Pad2)") (class "Default")
      (node (ref "C38") (pin "2") (pinfunction "2_2") (pintype "passive"))
      (node (ref "R162") (pin "1") (pinfunction "1_1") (pintype "passive"))
    )
    (net (code "21") (name "Net-(C44-Pad1)") (class "Default")
      (node (ref "C44") (pin "1") (pinfunction "1_1") (pintype "passive"))
      (node (ref "R26") (pin "1") (pinfunction "1_1") (pintype "passive"))
      (node (ref "R71") (pin "2") (pinfunction "2_2") (pintype "passive"))
      (node (ref "TP8") (pin "1") (pinfunction "1_1") (pintype "passive"))
    )
    (net (code "22") (name "Net-(C55-Pad2)") (class "Default")
      (node (ref "C55") (pin "2") (pinfunction "2_2") (pintype "passive"))
      (node (ref "R163") (pin "1") (pinfunction "1_1") (pintype "passive"))
    )
    (net (code "23") (name "Net-(C60-Pad1)") (class "Default")
      (node (ref "C60") (pin "1") (pinfunction "1_1") (pintype "passive"))
      (node (ref "R70") (pin "1") (pinfunction "1_1") (pintype "passive"))
      (node (ref "R73") (pin "2") (pinfunction "2_2") (pintype "passive"))
      (node (ref "TP27") (pin "1") (pinfunction "1_1") (pintype "passive"))
    )
    (net (code "24") (name "Net-(C96-Pad1)") (class "Default")
      (node (ref "C96") (pin "1") (pinfunction "1_1") (pintype "passive"))
      (node (ref "R164") (pin "1") (pinfunction "1_1") (pintype "passive"))
    )
    (net (code "25") (name "Net-(C97-Pad1)") (class "Default")
      (node (ref "C97") (pin "1") (pinfunction "1_1") (pintype "passive"))
      (node (ref "R165") (pin "1") (pinfunction "1_1") (pintype "passive"))
    )
    (net (code "26") (name "Net-(D2-A)") (class "Default")
      (node (ref "C30") (pin "1") (pinfunction "1_1") (pintype "passive"))
      (node (ref "C31") (pin "1") (pinfunction "1_1") (pintype "passive"))
      (node (ref "D2") (pin "2") (pinfunction "A_2") (pintype "passive"))
      (node (ref "M4") (pin "3") (pinfunction "SOURCE_3") (pintype "passive"))
    )
    (net (code "27") (name "Net-(D4-A)") (class "Default")
      (node (ref "D4") (pin "2") (pinfunction "A_2") (pintype "passive"))
      (node (ref "R5") (pin "1") (pinfunction "1_1") (pintype "passive"))
    )
    (net (code "28") (name "Net-(D4-K)") (class "Default")
      (node (ref "D4") (pin "1") (pinfunction "K_1") (pintype "passive"))
      (node (ref "M16") (pin "3") (pinfunction "DRAIN_3") (pintype "passive"))
    )
    (net (code "29") (name "Net-(D5-A)") (class "Default")
      (node (ref "D5") (pin "2") (pinfunction "A_2") (pintype "passive"))
      (node (ref "R31") (pin "1") (pinfunction "1_1") (pintype "passive"))
    )
    (net (code "30") (name "Net-(D6-A)") (class "Default")
      (node (ref "D6") (pin "2") (pinfunction "A_2") (pintype "passive"))
      (node (ref "R7") (pin "1") (pinfunction "1_1") (pintype "passive"))
    )
    (net (code "31") (name "Net-(D7-A)") (class "Default")
      (node (ref "D7") (pin "2") (pinfunction "A_2") (pintype "passive"))
      (node (ref "R6") (pin "1") (pinfunction "1_1") (pintype "passive"))
    )
    (net (code "32") (name "Net-(D14-A1)") (class "Default")
      (node (ref "D14") (pin "1") (pinfunction "A1_1") (pintype "passive"))
      (node (ref "R75") (pin "1") (pinfunction "1_1") (pintype "passive"))
    )
    (net (code "33") (name "Net-(D14-C)") (class "Default")
      (node (ref "D14") (pin "3") (pinfunction "C_3") (pintype "passive"))
      (node (ref "M1") (pin "3") (pinfunction "D2_3") (pintype "passive"))
      (node (ref "M5") (pin "1") (pinfunction "GATE_1") (pintype "passive"))
    )
    (net (code "34") (name "Net-(M1A-D1)") (class "Default")
      (node (ref "M1") (pin "6") (pinfunction "D1_6") (pintype "passive"))
      (node (ref "R36") (pin "1") (pinfunction "1_1") (pintype "passive"))
    )
    (net (code "35") (name "Net-(M1A-G1)") (class "Default")
      (node (ref "M1") (pin "2") (pinfunction "G1_2") (pintype "passive"))
      (node (ref "R38") (pin "2") (pinfunction "2_2") (pintype "passive"))
    )
    (net (code "36") (name "Net-(M1B-G2)") (class "Default")
      (node (ref "M1") (pin "5") (pinfunction "G2_5") (pintype "passive"))
      (node (ref "R76") (pin "2") (pinfunction "2_2") (pintype "passive"))
    )
    (net (code "37") (name "Net-(M3-SOURCE)") (class "Default")
      (node (ref "L2") (pin "1") (pinfunction "1_1") (pintype "passive"))
      (node (ref "M3") (pin "3") (pinfunction "SOURCE_3") (pintype "passive"))
    )
    (net (code "38") (name "Net-(M16-GATE)") (class "Default")
      (node (ref "C18") (pin "1") (pinfunction "1_1") (pintype "passive"))
      (node (ref "M16") (pin "1") (pinfunction "GATE_1") (pintype "passive"))
      (node (ref "R8") (pin "2") (pinfunction "2_2") (pintype "passive"))
      (node (ref "R9") (pin "2") (pinfunction "2_2") (pintype "passive"))
    )
    (net (code "39") (name "Net-(U4--)") (class "Default")
      (node (ref "R24") (pin "1") (pinfunction "1_1") (pintype "passive"))
      (node (ref "R28") (pin "2") (pinfunction "2_2") (pintype "passive"))
      (node (ref "U4") (pin "4") (pinfunction "-_4") (pintype "input"))
    )
    (net (code "40") (name "Net-(U8-K)") (class "Default")
      (node (ref "R28") (pin "1") (pinfunction "1_1") (pintype "passive"))
      (node (ref "U8") (pin "1") (pinfunction "K_1") (pintype "power_in"))
      (node (ref "U8") (pin "2") (pinfunction "REF_2") (pintype "power_in"))
    )
    (net (code "41") (name "Net-(U9-BOOT)") (class "Default")
      (node (ref "C38") (pin "1") (pinfunction "1_1") (pintype "passive"))
      (node (ref "U9") (pin "1") (pinfunction "BOOT_1") (pintype "output"))
    )
    (net (code "42") (name "Net-(U9-EN)") (class "Default")
      (node (ref "C36") (pin "1") (pinfunction "1_1") (pintype "passive"))
      (node (ref "C37") (pin "1") (pinfunction "1_1") (pintype "passive"))
      (node (ref "FB1") (pin "2") (pinfunction "2_2") (pintype "passive"))
      (node (ref "TP5") (pin "1") (pinfunction "1_1") (pintype "passive"))
      (node (ref "U9") (pin "2") (pinfunction "VIN_2") (pintype "input"))
      (node (ref "U9") (pin "3") (pinfunction "EN_3") (pintype "input"))
    )
    (net (code "43") (name "Net-(U9-RT{slash}SYNC)") (class "Default")
      (node (ref "R33") (pin "2") (pinfunction "2_2") (pintype "passive"))
      (node (ref "U9") (pin "4") (pinfunction "RT/SYNC_4") (pintype "input"))
    )
    (net (code "44") (name "Net-(U9-SS)") (class "Default")
      (node (ref "C43") (pin "1") (pinfunction "1_1") (pintype "passive"))
      (node (ref "U9") (pin "6") (pinfunction "SS_6") (pintype "output"))
    )
    (net (code "45") (name "Net-(U10-EN)") (class "Default")
      (node (ref "J4") (pin "2") (pinfunction "2_2") (pintype "passive"))
      (node (ref "R34") (pin "1") (pinfunction "1_1") (pintype "passive"))
      (node (ref "R36") (pin "2") (pinfunction "2_2") (pintype "passive"))
      (node (ref "U10") (pin "3") (pinfunction "EN_3") (pintype "input"))
    )
    (net (code "46") (name "Net-(U10-IN)") (class "Default")
      (node (ref "C45") (pin "1") (pinfunction "1_1") (pintype "passive"))
      (node (ref "C46") (pin "1") (pinfunction "1_1") (pintype "passive"))
      (node (ref "L4") (pin "2") (pinfunction "2_2") (pintype "passive"))
      (node (ref "R34") (pin "2") (pinfunction "2_2") (pintype "passive"))
      (node (ref "U10") (pin "1") (pinfunction "IN_1") (pintype "power_in"))
    )
    (net (code "47") (name "Net-(U14-BOOT)") (class "Default")
      (node (ref "C55") (pin "1") (pinfunction "1_1") (pintype "passive"))
      (node (ref "U14") (pin "1") (pinfunction "BOOT_1") (pintype "output"))
    )
    (net (code "48") (name "Net-(U14-EN)") (class "Default")
      (node (ref "C53") (pin "1") (pinfunction "1_1") (pintype "passive"))
      (node (ref "C54") (pin "1") (pinfunction "1_1") (pintype "passive"))
      (node (ref "FB2") (pin "2") (pinfunction "2_2") (pintype "passive"))
      (node (ref "TP24") (pin "1") (pinfunction "1_1") (pintype "passive"))
      (node (ref "U14") (pin "2") (pinfunction "VIN_2") (pintype "input"))
      (node (ref "U14") (pin "3") (pinfunction "EN_3") (pintype "input"))
    )
    (net (code "49") (name "Net-(U14-RT{slash}SYNC)") (class "Default")
      (node (ref "R72") (pin "2") (pinfunction "2_2") (pintype "passive"))
      (node (ref "U14") (pin "4") (pinfunction "RT/SYNC_4") (pintype "input"))
    )
    (net (code "50") (name "Net-(U14-SS)") (class "Default")
      (node (ref "C59") (pin "1") (pinfunction "1_1") (pintype "passive"))
      (node (ref "U14") (pin "6") (pinfunction "SS_6") (pintype "output"))
    )
    (net (code "51") (name "USB_5v") (class "Default")
      (node (ref "L4") (pin "1") (pinfunction "1_1") (pintype "passive"))
      (node (ref "R75") (pin "2") (pinfunction "2_2") (pintype "passive"))
    )
    (net (code "52") (name "VBAT") (class "Default")
      (node (ref "BATT1") (pin "1") (pinfunction "1_1") (pintype "passive"))
      (node (ref "M4") (pin "2") (pinfunction "DRAIN_2") (pintype "passive"))
    )
    (net (code "53") (name "VDC") (class "Default")
      (node (ref "C15") (pin "2") (pinfunction "2_2") (pintype "passive"))
      (node (ref "C16") (pin "2") (pinfunction "2_2") (pintype "passive"))
      (node (ref "C17") (pin "1") (pinfunction "1_1") (pintype "passive"))
      (node (ref "C29") (pin "1") (pinfunction "1_1") (pintype "passive"))
      (node (ref "C35") (pin "1") (pinfunction "1_1") (pintype "passive"))
      (node (ref "C52") (pin "1") (pinfunction "1_1") (pintype "passive"))
      (node (ref "FB1") (pin "1") (pinfunction "1_1") (pintype "passive"))
      (node (ref "FB2") (pin "1") (pinfunction "1_1") (pintype "passive"))
      (node (ref "L2") (pin "2") (pinfunction "2_2") (pintype "passive"))
      (node (ref "R27") (pin "2") (pinfunction "2_2") (pintype "passive"))
      (node (ref "R31") (pin "2") (pinfunction "2_2") (pintype "passive"))
      (node (ref "TP4") (pin "1") (pinfunction "1_1") (pintype "passive"))
    )
  )
)
